# cannon.net
KiCad netlist of a schematic drawn in EAGLE
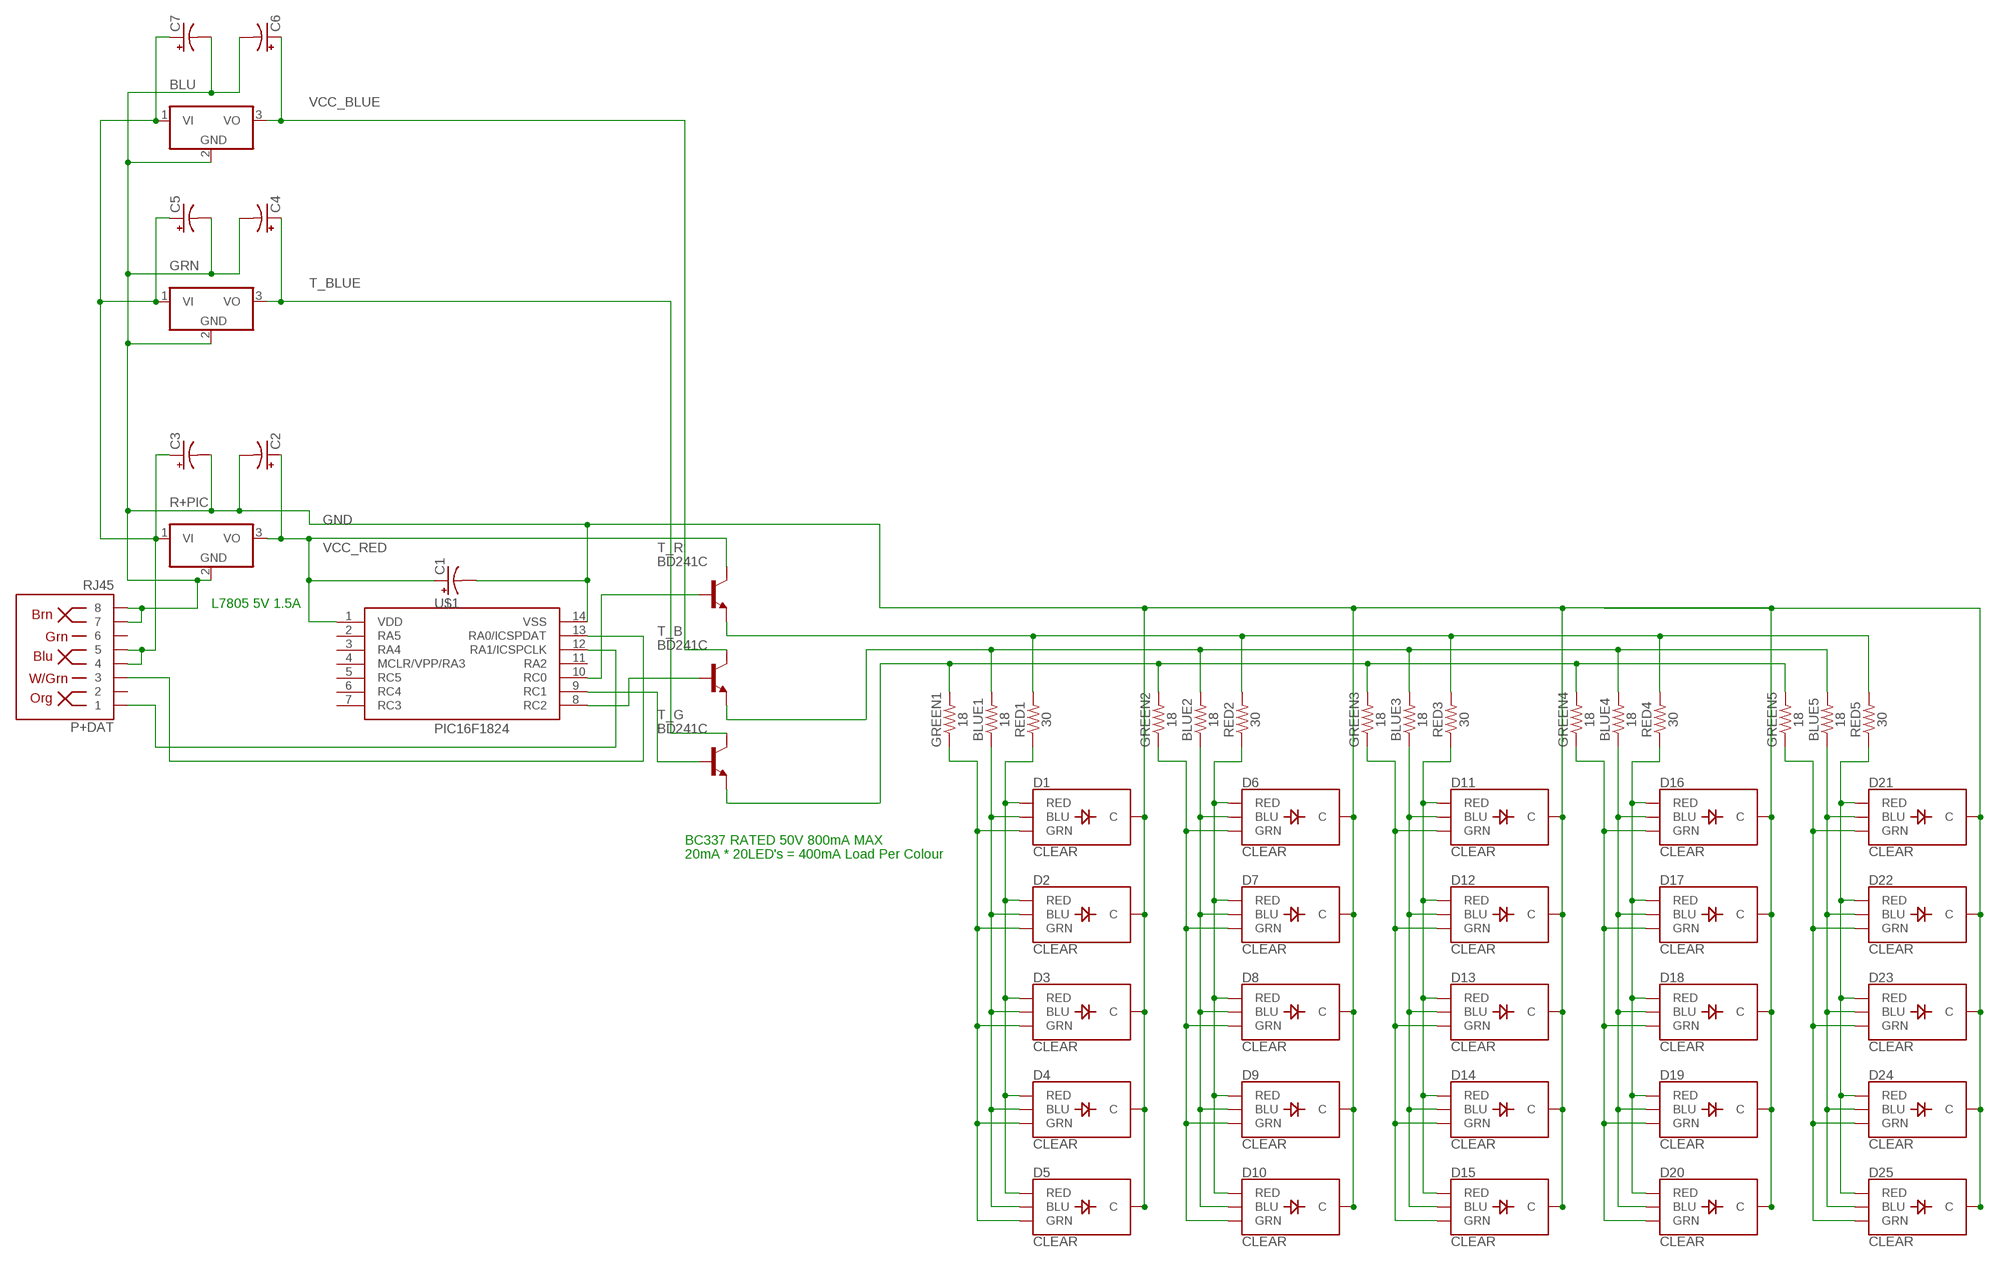
[diagram p0: schematic, sheet 1]

(export (version "E")
  (design (tool "Eeschema 10.0.6"))
  (components
    (comp (ref "BLU")
      (value "7805TV")
      (footprint "eagle-import:TO220V")
      (libsource (lib "eagle-import") (part "78TV05"))
    )
    (comp (ref "BLUE1")
      (value "18")
      (footprint "eagle-import:AXIAL-0.3")
      (libsource (lib "eagle-import") (part "10OHM-HORIZ-1/4W-1%"))
    )
    (comp (ref "BLUE2")
      (value "18")
      (footprint "eagle-import:AXIAL-0.3")
      (libsource (lib "eagle-import") (part "10OHM-HORIZ-1/4W-1%"))
    )
    (comp (ref "BLUE3")
      (value "18")
      (footprint "eagle-import:AXIAL-0.3")
      (libsource (lib "eagle-import") (part "10OHM-HORIZ-1/4W-1%"))
    )
    (comp (ref "BLUE4")
      (value "18")
      (footprint "eagle-import:AXIAL-0.3")
      (libsource (lib "eagle-import") (part "10OHM-HORIZ-1/4W-1%"))
    )
    (comp (ref "BLUE5")
      (value "18")
      (footprint "eagle-import:AXIAL-0.3")
      (libsource (lib "eagle-import") (part "10OHM-HORIZ-1/4W-1%"))
    )
    (comp (ref "C1")
      (value "0.1uF")
      (footprint "eagle-import:E2,5-6")
      (libsource (lib "eagle-import") (part "CAPACITOR-PE2.5-6"))
    )
    (comp (ref "C2")
      (value "0.1uF")
      (footprint "eagle-import:E2,5-6")
      (libsource (lib "eagle-import") (part "CAPACITOR-PE2.5-6"))
    )
    (comp (ref "C3")
      (value "0.33uF")
      (footprint "eagle-import:E2,5-6")
      (libsource (lib "eagle-import") (part "CAPACITOR-PE2.5-6"))
    )
    (comp (ref "C4")
      (value "0.1uF")
      (footprint "eagle-import:E2,5-6")
      (libsource (lib "eagle-import") (part "CAPACITOR-PE2.5-6"))
    )
    (comp (ref "C5")
      (value "0.33uF")
      (footprint "eagle-import:E2,5-6")
      (libsource (lib "eagle-import") (part "CAPACITOR-PE2.5-6"))
    )
    (comp (ref "C6")
      (value "0.1uF")
      (footprint "eagle-import:E2,5-6")
      (libsource (lib "eagle-import") (part "CAPACITOR-PE2.5-6"))
    )
    (comp (ref "C7")
      (value "0.33uF")
      (footprint "eagle-import:E2,5-6")
      (libsource (lib "eagle-import") (part "CAPACITOR-PE2.5-6"))
    )
    (comp (ref "D1")
      (value "CLEAR")
      (footprint "eagle-import:LED-RGB-THRU")
      (fields (field (name "SPICEPREFIX") "E"))
      (libsource (lib "eagle-import") (part "LED-RGB-CCCLEAR"))
    )
    (comp (ref "D2")
      (value "CLEAR")
      (footprint "eagle-import:LED-RGB-THRU")
      (libsource (lib "eagle-import") (part "LED-RGB-CCCLEAR"))
    )
    (comp (ref "D3")
      (value "CLEAR")
      (footprint "eagle-import:LED-RGB-THRU")
      (libsource (lib "eagle-import") (part "LED-RGB-CCCLEAR"))
    )
    (comp (ref "D4")
      (value "CLEAR")
      (footprint "eagle-import:LED-RGB-THRU")
      (libsource (lib "eagle-import") (part "LED-RGB-CCCLEAR"))
    )
    (comp (ref "D5")
      (value "CLEAR")
      (footprint "eagle-import:LED-RGB-THRU")
      (libsource (lib "eagle-import") (part "LED-RGB-CCCLEAR"))
    )
    (comp (ref "D6")
      (value "CLEAR")
      (footprint "eagle-import:LED-RGB-THRU")
      (libsource (lib "eagle-import") (part "LED-RGB-CCCLEAR"))
    )
    (comp (ref "D7")
      (value "CLEAR")
      (footprint "eagle-import:LED-RGB-THRU")
      (libsource (lib "eagle-import") (part "LED-RGB-CCCLEAR"))
    )
    (comp (ref "D8")
      (value "CLEAR")
      (footprint "eagle-import:LED-RGB-THRU")
      (libsource (lib "eagle-import") (part "LED-RGB-CCCLEAR"))
    )
    (comp (ref "D9")
      (value "CLEAR")
      (footprint "eagle-import:LED-RGB-THRU")
      (libsource (lib "eagle-import") (part "LED-RGB-CCCLEAR"))
    )
    (comp (ref "D10")
      (value "CLEAR")
      (footprint "eagle-import:LED-RGB-THRU")
      (libsource (lib "eagle-import") (part "LED-RGB-CCCLEAR"))
    )
    (comp (ref "D11")
      (value "CLEAR")
      (footprint "eagle-import:LED-RGB-THRU")
      (libsource (lib "eagle-import") (part "LED-RGB-CCCLEAR"))
    )
    (comp (ref "D12")
      (value "CLEAR")
      (footprint "eagle-import:LED-RGB-THRU")
      (libsource (lib "eagle-import") (part "LED-RGB-CCCLEAR"))
    )
    (comp (ref "D13")
      (value "CLEAR")
      (footprint "eagle-import:LED-RGB-THRU")
      (libsource (lib "eagle-import") (part "LED-RGB-CCCLEAR"))
    )
    (comp (ref "D14")
      (value "CLEAR")
      (footprint "eagle-import:LED-RGB-THRU")
      (libsource (lib "eagle-import") (part "LED-RGB-CCCLEAR"))
    )
    (comp (ref "D15")
      (value "CLEAR")
      (footprint "eagle-import:LED-RGB-THRU")
      (libsource (lib "eagle-import") (part "LED-RGB-CCCLEAR"))
    )
    (comp (ref "D16")
      (value "CLEAR")
      (footprint "eagle-import:LED-RGB-THRU")
      (libsource (lib "eagle-import") (part "LED-RGB-CCCLEAR"))
    )
    (comp (ref "D17")
      (value "CLEAR")
      (footprint "eagle-import:LED-RGB-THRU")
      (libsource (lib "eagle-import") (part "LED-RGB-CCCLEAR"))
    )
    (comp (ref "D18")
      (value "CLEAR")
      (footprint "eagle-import:LED-RGB-THRU")
      (libsource (lib "eagle-import") (part "LED-RGB-CCCLEAR"))
    )
    (comp (ref "D19")
      (value "CLEAR")
      (footprint "eagle-import:LED-RGB-THRU")
      (libsource (lib "eagle-import") (part "LED-RGB-CCCLEAR"))
    )
    (comp (ref "D20")
      (value "CLEAR")
      (footprint "eagle-import:LED-RGB-THRU")
      (libsource (lib "eagle-import") (part "LED-RGB-CCCLEAR"))
    )
    (comp (ref "D21")
      (value "CLEAR")
      (footprint "eagle-import:LED-RGB-THRU")
      (libsource (lib "eagle-import") (part "LED-RGB-CCCLEAR"))
    )
    (comp (ref "D22")
      (value "CLEAR")
      (footprint "eagle-import:LED-RGB-THRU")
      (libsource (lib "eagle-import") (part "LED-RGB-CCCLEAR"))
    )
    (comp (ref "D23")
      (value "CLEAR")
      (footprint "eagle-import:LED-RGB-THRU")
      (libsource (lib "eagle-import") (part "LED-RGB-CCCLEAR"))
    )
    (comp (ref "D24")
      (value "CLEAR")
      (footprint "eagle-import:LED-RGB-THRU")
      (libsource (lib "eagle-import") (part "LED-RGB-CCCLEAR"))
    )
    (comp (ref "D25")
      (value "CLEAR")
      (footprint "eagle-import:LED-RGB-THRU")
      (libsource (lib "eagle-import") (part "LED-RGB-CCCLEAR"))
    )
    (comp (ref "GREEN1")
      (value "18")
      (footprint "eagle-import:AXIAL-0.3")
      (libsource (lib "eagle-import") (part "10OHM-HORIZ-1/4W-1%"))
    )
    (comp (ref "GREEN2")
      (value "18")
      (footprint "eagle-import:AXIAL-0.3")
      (libsource (lib "eagle-import") (part "10OHM-HORIZ-1/4W-1%"))
    )
    (comp (ref "GREEN3")
      (value "18")
      (footprint "eagle-import:AXIAL-0.3")
      (libsource (lib "eagle-import") (part "10OHM-HORIZ-1/4W-1%"))
    )
    (comp (ref "GREEN4")
      (value "18")
      (footprint "eagle-import:AXIAL-0.3")
      (libsource (lib "eagle-import") (part "10OHM-HORIZ-1/4W-1%"))
    )
    (comp (ref "GREEN5")
      (value "18")
      (footprint "eagle-import:AXIAL-0.3")
      (libsource (lib "eagle-import") (part "10OHM-HORIZ-1/4W-1%"))
    )
    (comp (ref "GRN")
      (value "7805TV")
      (footprint "eagle-import:TO220V")
      (libsource (lib "eagle-import") (part "78TV05"))
    )
    (comp (ref "P+DAT")
      (value "RJ45")
      (footprint "eagle-import:RJ45-8")
      (libsource (lib "eagle-import") (part "RJ45-8"))
    )
    (comp (ref "R+PIC")
      (value "7805TV")
      (footprint "eagle-import:TO220V")
      (libsource (lib "eagle-import") (part "78TV05"))
    )
    (comp (ref "RED1")
      (value "30")
      (footprint "eagle-import:AXIAL-0.3")
      (libsource (lib "eagle-import") (part "10OHM-HORIZ-1/4W-1%"))
    )
    (comp (ref "RED2")
      (value "30")
      (footprint "eagle-import:AXIAL-0.3")
      (libsource (lib "eagle-import") (part "10OHM-HORIZ-1/4W-1%"))
    )
    (comp (ref "RED3")
      (value "30")
      (footprint "eagle-import:AXIAL-0.3")
      (libsource (lib "eagle-import") (part "10OHM-HORIZ-1/4W-1%"))
    )
    (comp (ref "RED4")
      (value "30")
      (footprint "eagle-import:AXIAL-0.3")
      (libsource (lib "eagle-import") (part "10OHM-HORIZ-1/4W-1%"))
    )
    (comp (ref "RED5")
      (value "30")
      (footprint "eagle-import:AXIAL-0.3")
      (libsource (lib "eagle-import") (part "10OHM-HORIZ-1/4W-1%"))
    )
    (comp (ref "T_B")
      (value "BD241C")
      (footprint "eagle-import:TO220BV")
      (libsource (lib "eagle-import") (part "2SC1306"))
    )
    (comp (ref "T_G")
      (value "BD241C")
      (footprint "eagle-import:TO220BV")
      (libsource (lib "eagle-import") (part "2SC1306"))
    )
    (comp (ref "T_R")
      (value "BD241C")
      (footprint "eagle-import:TO220BV")
      (libsource (lib "eagle-import") (part "2SC1306"))
    )
    (comp (ref "U$1")
      (value "PIC16F1824")
      (footprint "eagle-import:DIP787W45P254L1905H533Q14B")
      (libsource (lib "eagle-import") (part "PIC16F1824"))
    )
  )
  (nets
    (net (code "1") (name "/GND") (class "Default")
      (node (ref "BLU") (pin "2") (pinfunction "GND_2") (pintype "passive"))
      (node (ref "C1") (pin "-") (pinfunction "-_-") (pintype "passive"))
      (node (ref "C2") (pin "-") (pinfunction "-_-") (pintype "passive"))
      (node (ref "C3") (pin "-") (pinfunction "-_-") (pintype "passive"))
      (node (ref "C4") (pin "-") (pinfunction "-_-") (pintype "passive"))
      (node (ref "C5") (pin "-") (pinfunction "-_-") (pintype "passive"))
      (node (ref "C6") (pin "-") (pinfunction "-_-") (pintype "passive"))
      (node (ref "C7") (pin "-") (pinfunction "-_-") (pintype "passive"))
      (node (ref "D1") (pin "2") (pinfunction "C_2") (pintype "bidirectional"))
      (node (ref "D10") (pin "2") (pinfunction "C_2") (pintype "bidirectional"))
      (node (ref "D11") (pin "2") (pinfunction "C_2") (pintype "bidirectional"))
      (node (ref "D12") (pin "2") (pinfunction "C_2") (pintype "bidirectional"))
      (node (ref "D13") (pin "2") (pinfunction "C_2") (pintype "bidirectional"))
      (node (ref "D14") (pin "2") (pinfunction "C_2") (pintype "bidirectional"))
      (node (ref "D15") (pin "2") (pinfunction "C_2") (pintype "bidirectional"))
      (node (ref "D16") (pin "2") (pinfunction "C_2") (pintype "bidirectional"))
      (node (ref "D17") (pin "2") (pinfunction "C_2") (pintype "bidirectional"))
      (node (ref "D18") (pin "2") (pinfunction "C_2") (pintype "bidirectional"))
      (node (ref "D19") (pin "2") (pinfunction "C_2") (pintype "bidirectional"))
      (node (ref "D2") (pin "2") (pinfunction "C_2") (pintype "bidirectional"))
      (node (ref "D20") (pin "2") (pinfunction "C_2") (pintype "bidirectional"))
      (node (ref "D21") (pin "2") (pinfunction "C_2") (pintype "bidirectional"))
      (node (ref "D22") (pin "2") (pinfunction "C_2") (pintype "bidirectional"))
      (node (ref "D23") (pin "2") (pinfunction "C_2") (pintype "bidirectional"))
      (node (ref "D24") (pin "2") (pinfunction "C_2") (pintype "bidirectional"))
      (node (ref "D25") (pin "2") (pinfunction "C_2") (pintype "bidirectional"))
      (node (ref "D3") (pin "2") (pinfunction "C_2") (pintype "bidirectional"))
      (node (ref "D4") (pin "2") (pinfunction "C_2") (pintype "bidirectional"))
      (node (ref "D5") (pin "2") (pinfunction "C_2") (pintype "bidirectional"))
      (node (ref "D6") (pin "2") (pinfunction "C_2") (pintype "bidirectional"))
      (node (ref "D7") (pin "2") (pinfunction "C_2") (pintype "bidirectional"))
      (node (ref "D8") (pin "2") (pinfunction "C_2") (pintype "bidirectional"))
      (node (ref "D9") (pin "2") (pinfunction "C_2") (pintype "bidirectional"))
      (node (ref "GRN") (pin "2") (pinfunction "GND_2") (pintype "passive"))
      (node (ref "P+DAT") (pin "7") (pinfunction "7_7") (pintype "bidirectional"))
      (node (ref "P+DAT") (pin "8") (pinfunction "8_8") (pintype "bidirectional"))
      (node (ref "R+PIC") (pin "2") (pinfunction "GND_2") (pintype "passive"))
      (node (ref "U$1") (pin "14") (pinfunction "VSS_14") (pintype "power_in"))
    )
    (net (code "2") (name "/T_BLUE") (class "Default")
      (node (ref "C4") (pin "+") (pinfunction "+_+") (pintype "passive"))
      (node (ref "GRN") (pin "3") (pinfunction "VO_3") (pintype "passive"))
      (node (ref "T_G") (pin "2") (pinfunction "C_2") (pintype "passive"))
    )
    (net (code "3") (name "/VCC_BLUE") (class "Default")
      (node (ref "BLU") (pin "3") (pinfunction "VO_3") (pintype "passive"))
      (node (ref "C6") (pin "+") (pinfunction "+_+") (pintype "passive"))
      (node (ref "T_B") (pin "2") (pinfunction "C_2") (pintype "passive"))
    )
    (net (code "4") (name "/VCC_RED") (class "Default")
      (node (ref "C1") (pin "+") (pinfunction "+_+") (pintype "passive"))
      (node (ref "C2") (pin "+") (pinfunction "+_+") (pintype "passive"))
      (node (ref "R+PIC") (pin "3") (pinfunction "VO_3") (pintype "passive"))
      (node (ref "T_R") (pin "2") (pinfunction "C_2") (pintype "passive"))
      (node (ref "U$1") (pin "1") (pinfunction "VDD_1") (pintype "power_in"))
    )
    (net (code "5") (name "Net-(BLU-VI)") (class "Default")
      (node (ref "BLU") (pin "1") (pinfunction "VI_1") (pintype "input"))
      (node (ref "C3") (pin "+") (pinfunction "+_+") (pintype "passive"))
      (node (ref "C5") (pin "+") (pinfunction "+_+") (pintype "passive"))
      (node (ref "C7") (pin "+") (pinfunction "+_+") (pintype "passive"))
      (node (ref "GRN") (pin "1") (pinfunction "VI_1") (pintype "input"))
      (node (ref "P+DAT") (pin "4") (pinfunction "4_4") (pintype "bidirectional"))
      (node (ref "P+DAT") (pin "5") (pinfunction "5_5") (pintype "bidirectional"))
      (node (ref "R+PIC") (pin "1") (pinfunction "VI_1") (pintype "input"))
    )
    (net (code "6") (name "Net-(BLUE1-1)") (class "Default")
      (node (ref "BLUE1") (pin "P$1") (pinfunction "1_P$1") (pintype "passive"))
      (node (ref "D1") (pin "4") (pinfunction "BLU_4") (pintype "bidirectional"))
      (node (ref "D2") (pin "4") (pinfunction "BLU_4") (pintype "bidirectional"))
      (node (ref "D3") (pin "4") (pinfunction "BLU_4") (pintype "bidirectional"))
      (node (ref "D4") (pin "4") (pinfunction "BLU_4") (pintype "bidirectional"))
      (node (ref "D5") (pin "4") (pinfunction "BLU_4") (pintype "bidirectional"))
    )
    (net (code "7") (name "Net-(BLUE1-2)") (class "Default")
      (node (ref "BLUE1") (pin "P$2") (pinfunction "2_P$2") (pintype "passive"))
      (node (ref "BLUE2") (pin "P$2") (pinfunction "2_P$2") (pintype "passive"))
      (node (ref "BLUE3") (pin "P$2") (pinfunction "2_P$2") (pintype "passive"))
      (node (ref "BLUE4") (pin "P$2") (pinfunction "2_P$2") (pintype "passive"))
      (node (ref "BLUE5") (pin "P$2") (pinfunction "2_P$2") (pintype "passive"))
      (node (ref "T_B") (pin "3") (pinfunction "E_3") (pintype "passive"))
    )
    (net (code "8") (name "Net-(BLUE2-1)") (class "Default")
      (node (ref "BLUE2") (pin "P$1") (pinfunction "1_P$1") (pintype "passive"))
      (node (ref "D10") (pin "4") (pinfunction "BLU_4") (pintype "bidirectional"))
      (node (ref "D6") (pin "4") (pinfunction "BLU_4") (pintype "bidirectional"))
      (node (ref "D7") (pin "4") (pinfunction "BLU_4") (pintype "bidirectional"))
      (node (ref "D8") (pin "4") (pinfunction "BLU_4") (pintype "bidirectional"))
      (node (ref "D9") (pin "4") (pinfunction "BLU_4") (pintype "bidirectional"))
    )
    (net (code "9") (name "Net-(BLUE3-1)") (class "Default")
      (node (ref "BLUE3") (pin "P$1") (pinfunction "1_P$1") (pintype "passive"))
      (node (ref "D11") (pin "4") (pinfunction "BLU_4") (pintype "bidirectional"))
      (node (ref "D12") (pin "4") (pinfunction "BLU_4") (pintype "bidirectional"))
      (node (ref "D13") (pin "4") (pinfunction "BLU_4") (pintype "bidirectional"))
      (node (ref "D14") (pin "4") (pinfunction "BLU_4") (pintype "bidirectional"))
      (node (ref "D15") (pin "4") (pinfunction "BLU_4") (pintype "bidirectional"))
    )
    (net (code "10") (name "Net-(BLUE4-1)") (class "Default")
      (node (ref "BLUE4") (pin "P$1") (pinfunction "1_P$1") (pintype "passive"))
      (node (ref "D16") (pin "4") (pinfunction "BLU_4") (pintype "bidirectional"))
      (node (ref "D17") (pin "4") (pinfunction "BLU_4") (pintype "bidirectional"))
      (node (ref "D18") (pin "4") (pinfunction "BLU_4") (pintype "bidirectional"))
      (node (ref "D19") (pin "4") (pinfunction "BLU_4") (pintype "bidirectional"))
      (node (ref "D20") (pin "4") (pinfunction "BLU_4") (pintype "bidirectional"))
    )
    (net (code "11") (name "Net-(BLUE5-1)") (class "Default")
      (node (ref "BLUE5") (pin "P$1") (pinfunction "1_P$1") (pintype "passive"))
      (node (ref "D21") (pin "4") (pinfunction "BLU_4") (pintype "bidirectional"))
      (node (ref "D22") (pin "4") (pinfunction "BLU_4") (pintype "bidirectional"))
      (node (ref "D23") (pin "4") (pinfunction "BLU_4") (pintype "bidirectional"))
      (node (ref "D24") (pin "4") (pinfunction "BLU_4") (pintype "bidirectional"))
      (node (ref "D25") (pin "4") (pinfunction "BLU_4") (pintype "bidirectional"))
    )
    (net (code "12") (name "Net-(D1-GRN)") (class "Default")
      (node (ref "D1") (pin "3") (pinfunction "GRN_3") (pintype "bidirectional"))
      (node (ref "D2") (pin "3") (pinfunction "GRN_3") (pintype "bidirectional"))
      (node (ref "D3") (pin "3") (pinfunction "GRN_3") (pintype "bidirectional"))
      (node (ref "D4") (pin "3") (pinfunction "GRN_3") (pintype "bidirectional"))
      (node (ref "D5") (pin "3") (pinfunction "GRN_3") (pintype "bidirectional"))
      (node (ref "GREEN1") (pin "P$1") (pinfunction "1_P$1") (pintype "passive"))
    )
    (net (code "13") (name "Net-(D1-RED)") (class "Default")
      (node (ref "D1") (pin "1") (pinfunction "RED_1") (pintype "bidirectional"))
      (node (ref "D2") (pin "1") (pinfunction "RED_1") (pintype "bidirectional"))
      (node (ref "D3") (pin "1") (pinfunction "RED_1") (pintype "bidirectional"))
      (node (ref "D4") (pin "1") (pinfunction "RED_1") (pintype "bidirectional"))
      (node (ref "D5") (pin "1") (pinfunction "RED_1") (pintype "bidirectional"))
      (node (ref "RED1") (pin "P$1") (pinfunction "1_P$1") (pintype "passive"))
    )
    (net (code "14") (name "Net-(D10-GRN)") (class "Default")
      (node (ref "D10") (pin "3") (pinfunction "GRN_3") (pintype "bidirectional"))
      (node (ref "D6") (pin "3") (pinfunction "GRN_3") (pintype "bidirectional"))
      (node (ref "D7") (pin "3") (pinfunction "GRN_3") (pintype "bidirectional"))
      (node (ref "D8") (pin "3") (pinfunction "GRN_3") (pintype "bidirectional"))
      (node (ref "D9") (pin "3") (pinfunction "GRN_3") (pintype "bidirectional"))
      (node (ref "GREEN2") (pin "P$1") (pinfunction "1_P$1") (pintype "passive"))
    )
    (net (code "15") (name "Net-(D10-RED)") (class "Default")
      (node (ref "D10") (pin "1") (pinfunction "RED_1") (pintype "bidirectional"))
      (node (ref "D6") (pin "1") (pinfunction "RED_1") (pintype "bidirectional"))
      (node (ref "D7") (pin "1") (pinfunction "RED_1") (pintype "bidirectional"))
      (node (ref "D8") (pin "1") (pinfunction "RED_1") (pintype "bidirectional"))
      (node (ref "D9") (pin "1") (pinfunction "RED_1") (pintype "bidirectional"))
      (node (ref "RED2") (pin "P$1") (pinfunction "1_P$1") (pintype "passive"))
    )
    (net (code "16") (name "Net-(D11-GRN)") (class "Default")
      (node (ref "D11") (pin "3") (pinfunction "GRN_3") (pintype "bidirectional"))
      (node (ref "D12") (pin "3") (pinfunction "GRN_3") (pintype "bidirectional"))
      (node (ref "D13") (pin "3") (pinfunction "GRN_3") (pintype "bidirectional"))
      (node (ref "D14") (pin "3") (pinfunction "GRN_3") (pintype "bidirectional"))
      (node (ref "D15") (pin "3") (pinfunction "GRN_3") (pintype "bidirectional"))
      (node (ref "GREEN3") (pin "P$1") (pinfunction "1_P$1") (pintype "passive"))
    )
    (net (code "17") (name "Net-(D11-RED)") (class "Default")
      (node (ref "D11") (pin "1") (pinfunction "RED_1") (pintype "bidirectional"))
      (node (ref "D12") (pin "1") (pinfunction "RED_1") (pintype "bidirectional"))
      (node (ref "D13") (pin "1") (pinfunction "RED_1") (pintype "bidirectional"))
      (node (ref "D14") (pin "1") (pinfunction "RED_1") (pintype "bidirectional"))
      (node (ref "D15") (pin "1") (pinfunction "RED_1") (pintype "bidirectional"))
      (node (ref "RED3") (pin "P$1") (pinfunction "1_P$1") (pintype "passive"))
    )
    (net (code "18") (name "Net-(D16-GRN)") (class "Default")
      (node (ref "D16") (pin "3") (pinfunction "GRN_3") (pintype "bidirectional"))
      (node (ref "D17") (pin "3") (pinfunction "GRN_3") (pintype "bidirectional"))
      (node (ref "D18") (pin "3") (pinfunction "GRN_3") (pintype "bidirectional"))
      (node (ref "D19") (pin "3") (pinfunction "GRN_3") (pintype "bidirectional"))
      (node (ref "D20") (pin "3") (pinfunction "GRN_3") (pintype "bidirectional"))
      (node (ref "GREEN4") (pin "P$1") (pinfunction "1_P$1") (pintype "passive"))
    )
    (net (code "19") (name "Net-(D16-RED)") (class "Default")
      (node (ref "D16") (pin "1") (pinfunction "RED_1") (pintype "bidirectional"))
      (node (ref "D17") (pin "1") (pinfunction "RED_1") (pintype "bidirectional"))
      (node (ref "D18") (pin "1") (pinfunction "RED_1") (pintype "bidirectional"))
      (node (ref "D19") (pin "1") (pinfunction "RED_1") (pintype "bidirectional"))
      (node (ref "D20") (pin "1") (pinfunction "RED_1") (pintype "bidirectional"))
      (node (ref "RED4") (pin "P$1") (pinfunction "1_P$1") (pintype "passive"))
    )
    (net (code "20") (name "Net-(D21-GRN)") (class "Default")
      (node (ref "D21") (pin "3") (pinfunction "GRN_3") (pintype "bidirectional"))
      (node (ref "D22") (pin "3") (pinfunction "GRN_3") (pintype "bidirectional"))
      (node (ref "D23") (pin "3") (pinfunction "GRN_3") (pintype "bidirectional"))
      (node (ref "D24") (pin "3") (pinfunction "GRN_3") (pintype "bidirectional"))
      (node (ref "D25") (pin "3") (pinfunction "GRN_3") (pintype "bidirectional"))
      (node (ref "GREEN5") (pin "P$1") (pinfunction "1_P$1") (pintype "passive"))
    )
    (net (code "21") (name "Net-(D21-RED)") (class "Default")
      (node (ref "D21") (pin "1") (pinfunction "RED_1") (pintype "bidirectional"))
      (node (ref "D22") (pin "1") (pinfunction "RED_1") (pintype "bidirectional"))
      (node (ref "D23") (pin "1") (pinfunction "RED_1") (pintype "bidirectional"))
      (node (ref "D24") (pin "1") (pinfunction "RED_1") (pintype "bidirectional"))
      (node (ref "D25") (pin "1") (pinfunction "RED_1") (pintype "bidirectional"))
      (node (ref "RED5") (pin "P$1") (pinfunction "1_P$1") (pintype "passive"))
    )
    (net (code "22") (name "Net-(GREEN1-2)") (class "Default")
      (node (ref "GREEN1") (pin "P$2") (pinfunction "2_P$2") (pintype "passive"))
      (node (ref "GREEN2") (pin "P$2") (pinfunction "2_P$2") (pintype "passive"))
      (node (ref "GREEN3") (pin "P$2") (pinfunction "2_P$2") (pintype "passive"))
      (node (ref "GREEN4") (pin "P$2") (pinfunction "2_P$2") (pintype "passive"))
      (node (ref "GREEN5") (pin "P$2") (pinfunction "2_P$2") (pintype "passive"))
      (node (ref "T_G") (pin "3") (pinfunction "E_3") (pintype "passive"))
    )
    (net (code "23") (name "Net-(RED1-2)") (class "Default")
      (node (ref "RED1") (pin "P$2") (pinfunction "2_P$2") (pintype "passive"))
      (node (ref "RED2") (pin "P$2") (pinfunction "2_P$2") (pintype "passive"))
      (node (ref "RED3") (pin "P$2") (pinfunction "2_P$2") (pintype "passive"))
      (node (ref "RED4") (pin "P$2") (pinfunction "2_P$2") (pintype "passive"))
      (node (ref "RED5") (pin "P$2") (pinfunction "2_P$2") (pintype "passive"))
      (node (ref "T_R") (pin "3") (pinfunction "E_3") (pintype "passive"))
    )
    (net (code "24") (name "Net-(T_B-B)") (class "Default")
      (node (ref "T_B") (pin "1") (pinfunction "B_1") (pintype "passive"))
      (node (ref "U$1") (pin "8") (pinfunction "RC2_8") (pintype "bidirectional"))
    )
    (net (code "25") (name "Net-(T_G-B)") (class "Default")
      (node (ref "T_G") (pin "1") (pinfunction "B_1") (pintype "passive"))
      (node (ref "U$1") (pin "9") (pinfunction "RC1_9") (pintype "bidirectional"))
    )
    (net (code "26") (name "Net-(T_R-B)") (class "Default")
      (node (ref "T_R") (pin "1") (pinfunction "B_1") (pintype "passive"))
      (node (ref "U$1") (pin "10") (pinfunction "RC0_10") (pintype "bidirectional"))
    )
    (net (code "27") (name "Net-(U$1-RA0{slash}ICSPDAT)") (class "Default")
      (node (ref "P+DAT") (pin "3") (pinfunction "3_3") (pintype "bidirectional"))
      (node (ref "U$1") (pin "13") (pinfunction "RA0/ICSPDAT_13") (pintype "bidirectional"))
    )
    (net (code "28") (name "Net-(U$1-RA1{slash}ICSPCLK)") (class "Default")
      (node (ref "P+DAT") (pin "1") (pinfunction "1_1") (pintype "bidirectional"))
      (node (ref "U$1") (pin "12") (pinfunction "RA1/ICSPCLK_12") (pintype "bidirectional"))
    )
    (net (code "29") (name "unconnected-(P+DAT-Pad2)") (class "Default")
      (node (ref "P+DAT") (pin "2") (pinfunction "2_2") (pintype "bidirectional"))
    )
    (net (code "30") (name "unconnected-(P+DAT-Pad6)") (class "Default")
      (node (ref "P+DAT") (pin "6") (pinfunction "6_6") (pintype "bidirectional"))
    )
    (net (code "31") (name "unconnected-(U$1-MCLR{slash}VPP{slash}RA3-Pad4)") (class "Default")
      (node (ref "U$1") (pin "4") (pinfunction "MCLR/VPP/RA3_4") (pintype "bidirectional"))
    )
    (net (code "32") (name "unconnected-(U$1-RA2-Pad11)") (class "Default")
      (node (ref "U$1") (pin "11") (pinfunction "RA2_11") (pintype "bidirectional"))
    )
    (net (code "33") (name "unconnected-(U$1-RA4-Pad3)") (class "Default")
      (node (ref "U$1") (pin "3") (pinfunction "RA4_3") (pintype "bidirectional"))
    )
    (net (code "34") (name "unconnected-(U$1-RA5-Pad2)") (class "Default")
      (node (ref "U$1") (pin "2") (pinfunction "RA5_2") (pintype "bidirectional"))
    )
    (net (code "35") (name "unconnected-(U$1-RC3-Pad7)") (class "Default")
      (node (ref "U$1") (pin "7") (pinfunction "RC3_7") (pintype "bidirectional"))
    )
    (net (code "36") (name "unconnected-(U$1-RC4-Pad6)") (class "Default")
      (node (ref "U$1") (pin "6") (pinfunction "RC4_6") (pintype "bidirectional"))
    )
    (net (code "37") (name "unconnected-(U$1-RC5-Pad5)") (class "Default")
      (node (ref "U$1") (pin "5") (pinfunction "RC5_5") (pintype "bidirectional"))
    )
  )
)
